# percepcao_externa_sensores.net
KiCad netlist of a schematic drawn in Altium Designer
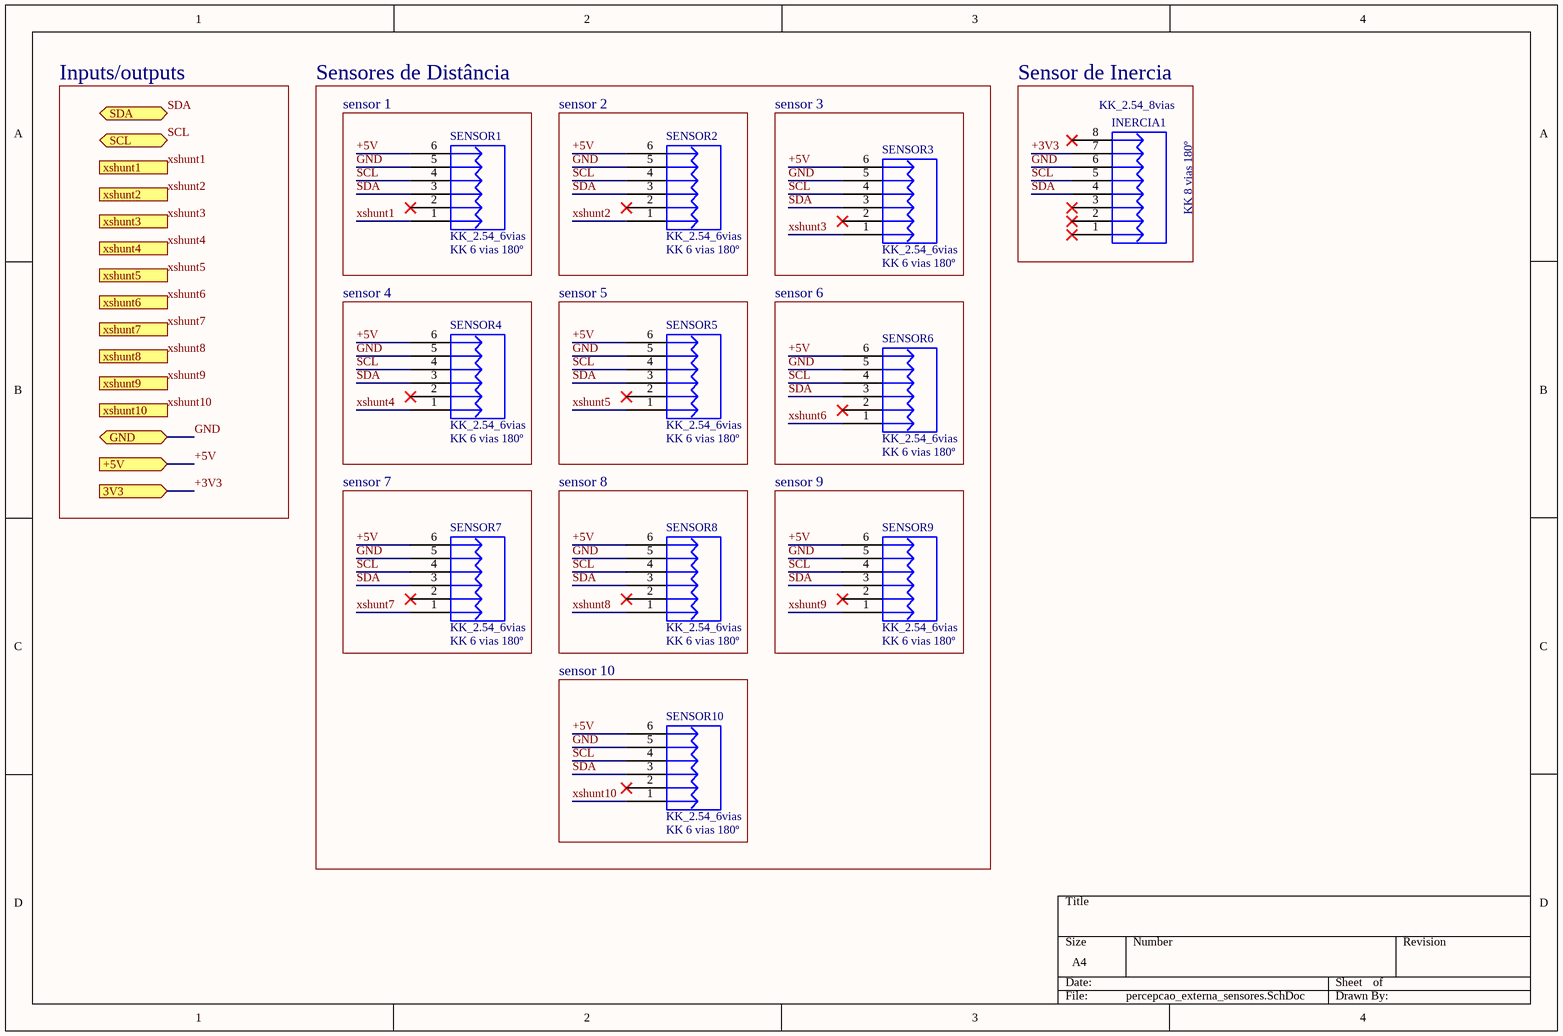
[diagram p0: percepcao_externa_sensores.SchDoc]

(export (version "E")
  (design (tool "Eeschema 10.0.6"))
  (components
    (comp (ref "INERCIA1")
      (value "KK_2.54_8vias")
      (footprint "KK_8vias_180°")
      (description "Conector KK 2.54mm 8 vias")
      (fields (field (name "VALOR") "KK 8 vias 180º"))
      (libsource (lib "Conectores_Sch") (part "KK_2.54_8vias"))
    )
    (comp (ref "SENSOR1")
      (value "KK_2.54_6vias")
      (footprint "KK_6vias_180°")
      (description "Conector KK 2.54mm 6 vias")
      (fields (field (name "VALOR") "KK 6 vias 180º"))
      (libsource (lib "Conectores_Sch") (part "KK_2.54_6vias"))
    )
    (comp (ref "SENSOR2")
      (value "KK_2.54_6vias")
      (footprint "KK_6vias_180°")
      (description "Conector KK 2.54mm 6 vias")
      (fields (field (name "VALOR") "KK 6 vias 180º"))
      (libsource (lib "Conectores_Sch") (part "KK_2.54_6vias"))
    )
    (comp (ref "SENSOR3")
      (value "KK_2.54_6vias")
      (footprint "KK_6vias_180°")
      (description "Conector KK 2.54mm 6 vias")
      (fields (field (name "VALOR") "KK 6 vias 180º"))
      (libsource (lib "Conectores_Sch") (part "KK_2.54_6vias"))
    )
    (comp (ref "SENSOR4")
      (value "KK_2.54_6vias")
      (footprint "KK_6vias_180°")
      (description "Conector KK 2.54mm 6 vias")
      (fields (field (name "VALOR") "KK 6 vias 180º"))
      (libsource (lib "Conectores_Sch") (part "KK_2.54_6vias"))
    )
    (comp (ref "SENSOR5")
      (value "KK_2.54_6vias")
      (footprint "KK_6vias_180°")
      (description "Conector KK 2.54mm 6 vias")
      (fields (field (name "VALOR") "KK 6 vias 180º"))
      (libsource (lib "Conectores_Sch") (part "KK_2.54_6vias"))
    )
    (comp (ref "SENSOR6")
      (value "KK_2.54_6vias")
      (footprint "KK_6vias_180°")
      (description "Conector KK 2.54mm 6 vias")
      (fields (field (name "VALOR") "KK 6 vias 180º"))
      (libsource (lib "Conectores_Sch") (part "KK_2.54_6vias"))
    )
    (comp (ref "SENSOR7")
      (value "KK_2.54_6vias")
      (footprint "KK_6vias_180°")
      (description "Conector KK 2.54mm 6 vias")
      (fields (field (name "VALOR") "KK 6 vias 180º"))
      (libsource (lib "Conectores_Sch") (part "KK_2.54_6vias"))
    )
    (comp (ref "SENSOR8")
      (value "KK_2.54_6vias")
      (footprint "KK_6vias_180°")
      (description "Conector KK 2.54mm 6 vias")
      (fields (field (name "VALOR") "KK 6 vias 180º"))
      (libsource (lib "Conectores_Sch") (part "KK_2.54_6vias"))
    )
    (comp (ref "SENSOR9")
      (value "KK_2.54_6vias")
      (footprint "KK_6vias_180°")
      (description "Conector KK 2.54mm 6 vias")
      (fields (field (name "VALOR") "KK 6 vias 180º"))
      (libsource (lib "Conectores_Sch") (part "KK_2.54_6vias"))
    )
    (comp (ref "SENSOR10")
      (value "KK_2.54_6vias")
      (footprint "KK_6vias_180°")
      (description "Conector KK 2.54mm 6 vias")
      (fields (field (name "VALOR") "KK 6 vias 180º"))
      (libsource (lib "Conectores_Sch") (part "KK_2.54_6vias"))
    )
  )
  (nets
    (net (code "1") (name "/+3V3") (class "Default") (node (ref "INERCIA1") (pin "7") (pintype "passive")))
    (net (code "2") (name "/+5V") (class "Default")
      (node (ref "SENSOR1") (pin "6") (pintype "passive"))
      (node (ref "SENSOR10") (pin "6") (pintype "passive"))
      (node (ref "SENSOR2") (pin "6") (pintype "passive"))
      (node (ref "SENSOR3") (pin "6") (pintype "passive"))
      (node (ref "SENSOR4") (pin "6") (pintype "passive"))
      (node (ref "SENSOR5") (pin "6") (pintype "passive"))
      (node (ref "SENSOR6") (pin "6") (pintype "passive"))
      (node (ref "SENSOR7") (pin "6") (pintype "passive"))
      (node (ref "SENSOR8") (pin "6") (pintype "passive"))
      (node (ref "SENSOR9") (pin "6") (pintype "passive"))
    )
    (net (code "3") (name "/GND") (class "Default")
      (node (ref "INERCIA1") (pin "6") (pintype "passive"))
      (node (ref "SENSOR1") (pin "5") (pintype "passive"))
      (node (ref "SENSOR10") (pin "5") (pintype "passive"))
      (node (ref "SENSOR2") (pin "5") (pintype "passive"))
      (node (ref "SENSOR3") (pin "5") (pintype "passive"))
      (node (ref "SENSOR4") (pin "5") (pintype "passive"))
      (node (ref "SENSOR5") (pin "5") (pintype "passive"))
      (node (ref "SENSOR6") (pin "5") (pintype "passive"))
      (node (ref "SENSOR7") (pin "5") (pintype "passive"))
      (node (ref "SENSOR8") (pin "5") (pintype "passive"))
      (node (ref "SENSOR9") (pin "5") (pintype "passive"))
    )
    (net (code "4") (name "/SCL") (class "Default")
      (node (ref "INERCIA1") (pin "5") (pintype "passive"))
      (node (ref "SENSOR1") (pin "4") (pintype "passive"))
      (node (ref "SENSOR10") (pin "4") (pintype "passive"))
      (node (ref "SENSOR2") (pin "4") (pintype "passive"))
      (node (ref "SENSOR3") (pin "4") (pintype "passive"))
      (node (ref "SENSOR4") (pin "4") (pintype "passive"))
      (node (ref "SENSOR5") (pin "4") (pintype "passive"))
      (node (ref "SENSOR6") (pin "4") (pintype "passive"))
      (node (ref "SENSOR7") (pin "4") (pintype "passive"))
      (node (ref "SENSOR8") (pin "4") (pintype "passive"))
      (node (ref "SENSOR9") (pin "4") (pintype "passive"))
    )
    (net (code "5") (name "/SDA") (class "Default")
      (node (ref "INERCIA1") (pin "4") (pintype "passive"))
      (node (ref "SENSOR1") (pin "3") (pintype "passive"))
      (node (ref "SENSOR10") (pin "3") (pintype "passive"))
      (node (ref "SENSOR2") (pin "3") (pintype "passive"))
      (node (ref "SENSOR3") (pin "3") (pintype "passive"))
      (node (ref "SENSOR4") (pin "3") (pintype "passive"))
      (node (ref "SENSOR5") (pin "3") (pintype "passive"))
      (node (ref "SENSOR6") (pin "3") (pintype "passive"))
      (node (ref "SENSOR7") (pin "3") (pintype "passive"))
      (node (ref "SENSOR8") (pin "3") (pintype "passive"))
      (node (ref "SENSOR9") (pin "3") (pintype "passive"))
    )
    (net (code "6") (name "/xshunt1") (class "Default") (node (ref "SENSOR1") (pin "1") (pintype "passive")))
    (net (code "7") (name "/xshunt2") (class "Default") (node (ref "SENSOR2") (pin "1") (pintype "passive")))
    (net (code "8") (name "/xshunt3") (class "Default") (node (ref "SENSOR3") (pin "1") (pintype "passive")))
    (net (code "9") (name "/xshunt4") (class "Default") (node (ref "SENSOR4") (pin "1") (pintype "passive")))
    (net (code "10") (name "/xshunt5") (class "Default") (node (ref "SENSOR5") (pin "1") (pintype "passive")))
    (net (code "11") (name "/xshunt6") (class "Default") (node (ref "SENSOR6") (pin "1") (pintype "passive")))
    (net (code "12") (name "/xshunt7") (class "Default") (node (ref "SENSOR7") (pin "1") (pintype "passive")))
    (net (code "13") (name "/xshunt8") (class "Default") (node (ref "SENSOR8") (pin "1") (pintype "passive")))
    (net (code "14") (name "/xshunt9") (class "Default") (node (ref "SENSOR9") (pin "1") (pintype "passive")))
    (net (code "15") (name "/xshunt10") (class "Default")
      (node (ref "SENSOR10") (pin "1") (pintype "passive"))
    )
    (net (code "16") (name "unconnected-(INERCIA1-Pad1)") (class "Default")
      (node (ref "INERCIA1") (pin "1") (pintype "passive+no_connect"))
    )
    (net (code "17") (name "unconnected-(INERCIA1-Pad2)") (class "Default")
      (node (ref "INERCIA1") (pin "2") (pintype "passive+no_connect"))
    )
    (net (code "18") (name "unconnected-(INERCIA1-Pad3)") (class "Default")
      (node (ref "INERCIA1") (pin "3") (pintype "passive+no_connect"))
    )
    (net (code "19") (name "unconnected-(INERCIA1-Pad8)") (class "Default")
      (node (ref "INERCIA1") (pin "8") (pintype "passive+no_connect"))
    )
    (net (code "20") (name "unconnected-(SENSOR1-Pad2)") (class "Default")
      (node (ref "SENSOR1") (pin "2") (pintype "passive+no_connect"))
    )
    (net (code "21") (name "unconnected-(SENSOR2-Pad2)") (class "Default")
      (node (ref "SENSOR2") (pin "2") (pintype "passive+no_connect"))
    )
    (net (code "22") (name "unconnected-(SENSOR3-Pad2)") (class "Default")
      (node (ref "SENSOR3") (pin "2") (pintype "passive+no_connect"))
    )
    (net (code "23") (name "unconnected-(SENSOR4-Pad2)") (class "Default")
      (node (ref "SENSOR4") (pin "2") (pintype "passive+no_connect"))
    )
    (net (code "24") (name "unconnected-(SENSOR5-Pad2)") (class "Default")
      (node (ref "SENSOR5") (pin "2") (pintype "passive+no_connect"))
    )
    (net (code "25") (name "unconnected-(SENSOR6-Pad2)") (class "Default")
      (node (ref "SENSOR6") (pin "2") (pintype "passive+no_connect"))
    )
    (net (code "26") (name "unconnected-(SENSOR7-Pad2)") (class "Default")
      (node (ref "SENSOR7") (pin "2") (pintype "passive+no_connect"))
    )
    (net (code "27") (name "unconnected-(SENSOR8-Pad2)") (class "Default")
      (node (ref "SENSOR8") (pin "2") (pintype "passive+no_connect"))
    )
    (net (code "28") (name "unconnected-(SENSOR9-Pad2)") (class "Default")
      (node (ref "SENSOR9") (pin "2") (pintype "passive+no_connect"))
    )
    (net (code "29") (name "unconnected-(SENSOR10-Pad2)") (class "Default")
      (node (ref "SENSOR10") (pin "2") (pintype "passive+no_connect"))
    )
  )
)
